# LightController.net
KiCad netlist of a schematic drawn in EAGLE
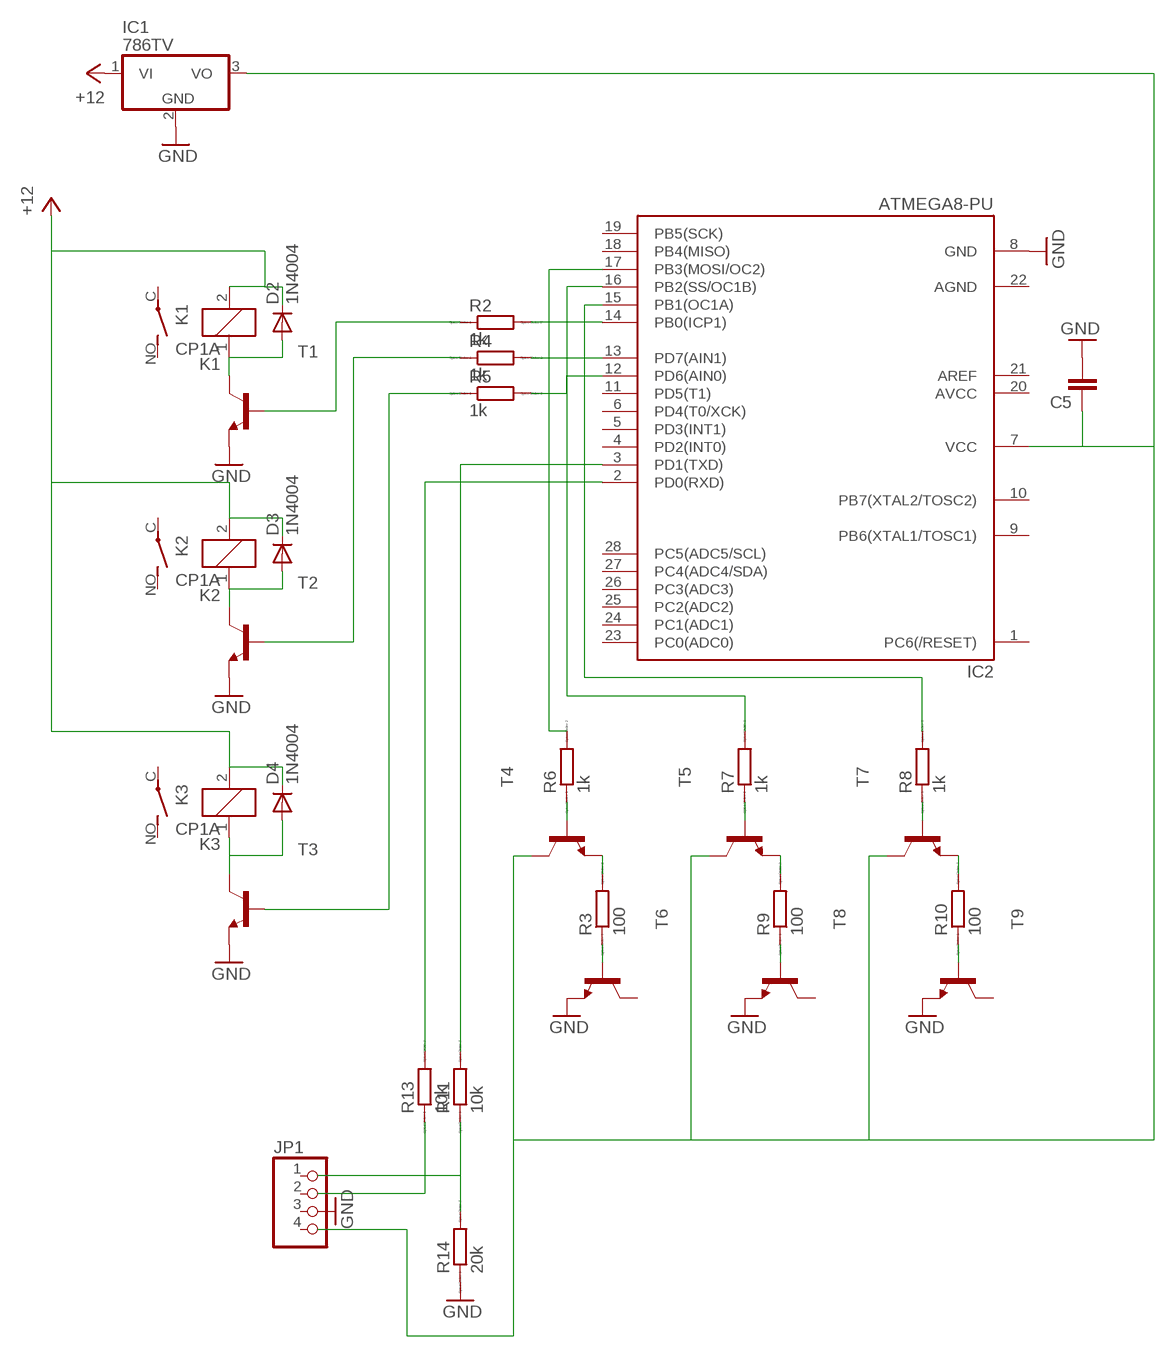
[diagram p0: schematic, sheet 1]

(export (version "E")
  (design (tool "Eeschema 10.0.6"))
  (components
    (comp (ref "C5")
      (value "C2,5-3")
      (footprint "eagle-import:C2.5-3")
      (libsource (lib "eagle-import") (part "C2,5-3"))
    )
    (comp (ref "D2")
      (value "1N4004")
      (footprint "eagle-import:DO41-10")
      (libsource (lib "eagle-import") (part "1N4004"))
    )
    (comp (ref "D3")
      (value "1N4004")
      (footprint "eagle-import:DO41-10")
      (libsource (lib "eagle-import") (part "1N4004"))
    )
    (comp (ref "D4")
      (value "1N4004")
      (footprint "eagle-import:DO41-10")
      (libsource (lib "eagle-import") (part "1N4004"))
    )
    (comp (ref "IC1")
      (value "786TV")
      (footprint "eagle-import:TO220V")
      (libsource (lib "eagle-import") (part "78TV6"))
    )
    (comp (ref "IC2")
      (value "ATMEGA8-PU")
      (footprint "eagle-import:DIL28-3")
      (libsource (lib "eagle-import") (part "ATMEGA8-PU"))
    )
    (comp (ref "JP1")
      (value "PINHD-1X4")
      (footprint "eagle-import:1X04")
      (libsource (lib "eagle-import") (part "PINHD-1X4"))
    )
    (comp (ref "K1")
      (value "CP1A")
      (footprint "eagle-import:CP1A")
      (fields (field (name "MF") "AROMAT/ MATSUSHITA") (field (name "MPN") "CP1A-12V"))
      (libsource (lib "eagle-import") (part "CP1A"))
    )
    (comp (ref "K2")
      (value "CP1A")
      (footprint "eagle-import:CP1A")
      (fields (field (name "MF") "AROMAT/ MATSUSHITA") (field (name "MPN") "CP1A-12V"))
      (libsource (lib "eagle-import") (part "CP1A"))
    )
    (comp (ref "K3")
      (value "CP1A")
      (footprint "eagle-import:CP1A")
      (fields (field (name "MF") "AROMAT/ MATSUSHITA") (field (name "MPN") "CP1A-12V"))
      (libsource (lib "eagle-import") (part "CP1A"))
    )
    (comp (ref "R2")
      (value "1k")
      (footprint "eagle-import:0204_7")
      (libsource (lib "eagle-import") (part "R0204/7"))
    )
    (comp (ref "R3")
      (value "100")
      (footprint "eagle-import:0204_7")
      (libsource (lib "eagle-import") (part "R0204/7"))
    )
    (comp (ref "R4")
      (value "1k")
      (footprint "eagle-import:0204_7")
      (libsource (lib "eagle-import") (part "R0204/7"))
    )
    (comp (ref "R5")
      (value "1k")
      (footprint "eagle-import:0204_7")
      (libsource (lib "eagle-import") (part "R0204/7"))
    )
    (comp (ref "R6")
      (value "1k")
      (footprint "eagle-import:0204_7")
      (libsource (lib "eagle-import") (part "R0204/7"))
    )
    (comp (ref "R7")
      (value "1k")
      (footprint "eagle-import:0204_7")
      (libsource (lib "eagle-import") (part "R0204/7"))
    )
    (comp (ref "R8")
      (value "1k")
      (footprint "eagle-import:0204_7")
      (libsource (lib "eagle-import") (part "R0204/7"))
    )
    (comp (ref "R9")
      (value "100")
      (footprint "eagle-import:0204_7")
      (libsource (lib "eagle-import") (part "R0204/7"))
    )
    (comp (ref "R10")
      (value "100")
      (footprint "eagle-import:0204_7")
      (libsource (lib "eagle-import") (part "R0204/7"))
    )
    (comp (ref "R11")
      (value "10k")
      (footprint "eagle-import:0204_7")
      (libsource (lib "eagle-import") (part "R0204/7"))
    )
    (comp (ref "R13")
      (value "10k")
      (footprint "eagle-import:0204_7")
      (libsource (lib "eagle-import") (part "R0204/7"))
    )
    (comp (ref "R14")
      (value "20k")
      (footprint "eagle-import:0204_7")
      (libsource (lib "eagle-import") (part "R0204/7"))
    )
    (comp (ref "T1")
      (value "-NPN-TO92-EBC")
      (footprint "eagle-import:TO92-EBC")
      (libsource (lib "eagle-import") (part "-NPN-TO92-EBC"))
    )
    (comp (ref "T2")
      (value "-NPN-TO92-EBC")
      (footprint "eagle-import:TO92-EBC")
      (libsource (lib "eagle-import") (part "-NPN-TO92-EBC"))
    )
    (comp (ref "T3")
      (value "-NPN-TO92-EBC")
      (footprint "eagle-import:TO92-EBC")
      (libsource (lib "eagle-import") (part "-NPN-TO92-EBC"))
    )
    (comp (ref "T4")
      (value "-NPN-TO92-EBC")
      (footprint "eagle-import:TO92-EBC")
      (libsource (lib "eagle-import") (part "-NPN-TO92-EBC"))
    )
    (comp (ref "T5")
      (value "-NPN-TO92-EBC")
      (footprint "eagle-import:TO92-EBC")
      (libsource (lib "eagle-import") (part "-NPN-TO92-EBC"))
    )
    (comp (ref "T6")
      (value "BF420-NPN-TO92-BCE")
      (footprint "eagle-import:TO92-BCE")
      (libsource (lib "eagle-import") (part "-NPN-TO92-BCEBF420"))
    )
    (comp (ref "T7")
      (value "-NPN-TO92-EBC")
      (footprint "eagle-import:TO92-EBC")
      (libsource (lib "eagle-import") (part "-NPN-TO92-EBC"))
    )
    (comp (ref "T8")
      (value "BF420-NPN-TO92-BCE")
      (footprint "eagle-import:TO92-BCE")
      (libsource (lib "eagle-import") (part "-NPN-TO92-BCEBF420"))
    )
    (comp (ref "T9")
      (value "BF420-NPN-TO92-BCE")
      (footprint "eagle-import:TO92-BCE")
      (libsource (lib "eagle-import") (part "-NPN-TO92-BCEBF420"))
    )
  )
  (nets
    (net (code "1") (name "+12") (class "Default")
      (node (ref "D2") (pin "C") (pinfunction "C_C") (pintype "passive"))
      (node (ref "D3") (pin "C") (pinfunction "C_C") (pintype "passive"))
      (node (ref "D4") (pin "C") (pinfunction "C_C") (pintype "passive"))
      (node (ref "IC1") (pin "1") (pinfunction "VI_1") (pintype "input"))
      (node (ref "K1") (pin "2") (pinfunction "2_2") (pintype "passive"))
      (node (ref "K2") (pin "2") (pinfunction "2_2") (pintype "passive"))
      (node (ref "K3") (pin "2") (pinfunction "2_2") (pintype "passive"))
    )
    (net (code "2") (name "/AGND") (class "Default")
      (node (ref "IC2") (pin "22") (pinfunction "AGND_22") (pintype "power_in"))
    )
    (net (code "3") (name "GND") (class "Default")
      (node (ref "C5") (pin "2") (pinfunction "2_2") (pintype "passive"))
      (node (ref "IC1") (pin "2") (pinfunction "GND_2") (pintype "passive"))
      (node (ref "IC2") (pin "8") (pinfunction "GND_8") (pintype "power_in"))
      (node (ref "R14") (pin "1") (pinfunction "1_1") (pintype "passive"))
      (node (ref "T1") (pin "E") (pinfunction "E_E") (pintype "passive"))
      (node (ref "T2") (pin "E") (pinfunction "E_E") (pintype "passive"))
      (node (ref "T3") (pin "E") (pinfunction "E_E") (pintype "passive"))
      (node (ref "T6") (pin "E") (pinfunction "E_E") (pintype "passive"))
      (node (ref "T8") (pin "E") (pinfunction "E_E") (pintype "passive"))
      (node (ref "T9") (pin "E") (pinfunction "E_E") (pintype "passive"))
    )
    (net (code "4") (name "Net-(D2-PadA)") (class "Default")
      (node (ref "D2") (pin "A") (pinfunction "A_A") (pintype "passive"))
      (node (ref "K1") (pin "1") (pinfunction "1_1") (pintype "passive"))
      (node (ref "T1") (pin "C") (pinfunction "C_C") (pintype "passive"))
    )
    (net (code "5") (name "Net-(D3-PadA)") (class "Default")
      (node (ref "D3") (pin "A") (pinfunction "A_A") (pintype "passive"))
      (node (ref "K2") (pin "1") (pinfunction "1_1") (pintype "passive"))
      (node (ref "T2") (pin "C") (pinfunction "C_C") (pintype "passive"))
    )
    (net (code "6") (name "Net-(D4-PadA)") (class "Default")
      (node (ref "D4") (pin "A") (pinfunction "A_A") (pintype "passive"))
      (node (ref "K3") (pin "1") (pinfunction "1_1") (pintype "passive"))
      (node (ref "T3") (pin "C") (pinfunction "C_C") (pintype "passive"))
    )
    (net (code "7") (name "Net-(IC1-VO)") (class "Default")
      (node (ref "C5") (pin "1") (pinfunction "1_1") (pintype "passive"))
      (node (ref "IC1") (pin "3") (pinfunction "VO_3") (pintype "passive"))
      (node (ref "IC2") (pin "7") (pinfunction "VCC_7") (pintype "power_in"))
      (node (ref "T4") (pin "C") (pinfunction "C_C") (pintype "passive"))
      (node (ref "T5") (pin "C") (pinfunction "C_C") (pintype "passive"))
      (node (ref "T7") (pin "C") (pinfunction "C_C") (pintype "passive"))
    )
    (net (code "8") (name "Net-(IC2-PB0(ICP1))") (class "Default")
      (node (ref "IC2") (pin "14") (pinfunction "PB0(ICP1)_14") (pintype "bidirectional"))
      (node (ref "R2") (pin "2") (pinfunction "2_2") (pintype "passive"))
    )
    (net (code "9") (name "Net-(IC2-PB1(OC1A))") (class "Default")
      (node (ref "IC2") (pin "15") (pinfunction "PB1(OC1A)_15") (pintype "bidirectional"))
      (node (ref "R8") (pin "2") (pinfunction "2_2") (pintype "passive"))
    )
    (net (code "10") (name "Net-(IC2-PB2(SS{slash}OC1B))") (class "Default")
      (node (ref "IC2") (pin "16") (pinfunction "PB2(SS/OC1B)_16") (pintype "bidirectional"))
      (node (ref "R7") (pin "2") (pinfunction "2_2") (pintype "passive"))
    )
    (net (code "11") (name "Net-(IC2-PB3(MOSI{slash}OC2))") (class "Default")
      (node (ref "IC2") (pin "17") (pinfunction "PB3(MOSI/OC2)_17") (pintype "bidirectional"))
      (node (ref "R6") (pin "2") (pinfunction "2_2") (pintype "passive"))
    )
    (net (code "12") (name "Net-(IC2-PD0(RXD))") (class "Default")
      (node (ref "IC2") (pin "2") (pinfunction "PD0(RXD)_2") (pintype "bidirectional"))
      (node (ref "R13") (pin "2") (pinfunction "2_2") (pintype "passive"))
    )
    (net (code "13") (name "Net-(IC2-PD1(TXD))") (class "Default")
      (node (ref "IC2") (pin "3") (pinfunction "PD1(TXD)_3") (pintype "bidirectional"))
      (node (ref "R11") (pin "2") (pinfunction "2_2") (pintype "passive"))
    )
    (net (code "14") (name "Net-(IC2-PD6(AIN0))") (class "Default")
      (node (ref "IC2") (pin "12") (pinfunction "PD6(AIN0)_12") (pintype "bidirectional"))
      (node (ref "R5") (pin "2") (pinfunction "2_2") (pintype "passive"))
    )
    (net (code "15") (name "Net-(IC2-PD7(AIN1))") (class "Default")
      (node (ref "IC2") (pin "13") (pinfunction "PD7(AIN1)_13") (pintype "bidirectional"))
      (node (ref "R4") (pin "2") (pinfunction "2_2") (pintype "passive"))
    )
    (net (code "16") (name "Net-(R2-Pad1)") (class "Default")
      (node (ref "R2") (pin "1") (pinfunction "1_1") (pintype "passive"))
      (node (ref "T1") (pin "B") (pinfunction "B_B") (pintype "passive"))
    )
    (net (code "17") (name "Net-(R3-Pad1)") (class "Default")
      (node (ref "R3") (pin "1") (pinfunction "1_1") (pintype "passive"))
      (node (ref "T6") (pin "B") (pinfunction "B_B") (pintype "passive"))
    )
    (net (code "18") (name "Net-(R3-Pad2)") (class "Default")
      (node (ref "R3") (pin "2") (pinfunction "2_2") (pintype "passive"))
      (node (ref "T4") (pin "E") (pinfunction "E_E") (pintype "passive"))
    )
    (net (code "19") (name "Net-(R4-Pad1)") (class "Default")
      (node (ref "R4") (pin "1") (pinfunction "1_1") (pintype "passive"))
      (node (ref "T2") (pin "B") (pinfunction "B_B") (pintype "passive"))
    )
    (net (code "20") (name "Net-(R5-Pad1)") (class "Default")
      (node (ref "R5") (pin "1") (pinfunction "1_1") (pintype "passive"))
      (node (ref "T3") (pin "B") (pinfunction "B_B") (pintype "passive"))
    )
    (net (code "21") (name "Net-(R6-Pad1)") (class "Default")
      (node (ref "R6") (pin "1") (pinfunction "1_1") (pintype "passive"))
      (node (ref "T4") (pin "B") (pinfunction "B_B") (pintype "passive"))
    )
    (net (code "22") (name "Net-(R7-Pad1)") (class "Default")
      (node (ref "R7") (pin "1") (pinfunction "1_1") (pintype "passive"))
      (node (ref "T5") (pin "B") (pinfunction "B_B") (pintype "passive"))
    )
    (net (code "23") (name "Net-(R8-Pad1)") (class "Default")
      (node (ref "R8") (pin "1") (pinfunction "1_1") (pintype "passive"))
      (node (ref "T7") (pin "B") (pinfunction "B_B") (pintype "passive"))
    )
    (net (code "24") (name "Net-(R9-Pad1)") (class "Default")
      (node (ref "R9") (pin "1") (pinfunction "1_1") (pintype "passive"))
      (node (ref "T8") (pin "B") (pinfunction "B_B") (pintype "passive"))
    )
    (net (code "25") (name "Net-(R9-Pad2)") (class "Default")
      (node (ref "R9") (pin "2") (pinfunction "2_2") (pintype "passive"))
      (node (ref "T5") (pin "E") (pinfunction "E_E") (pintype "passive"))
    )
    (net (code "26") (name "Net-(R10-Pad1)") (class "Default")
      (node (ref "R10") (pin "1") (pinfunction "1_1") (pintype "passive"))
      (node (ref "T9") (pin "B") (pinfunction "B_B") (pintype "passive"))
    )
    (net (code "27") (name "Net-(R10-Pad2)") (class "Default")
      (node (ref "R10") (pin "2") (pinfunction "2_2") (pintype "passive"))
      (node (ref "T7") (pin "E") (pinfunction "E_E") (pintype "passive"))
    )
    (net (code "28") (name "Net-(R11-Pad1)") (class "Default")
      (node (ref "R11") (pin "1") (pinfunction "1_1") (pintype "passive"))
      (node (ref "R14") (pin "2") (pinfunction "2_2") (pintype "passive"))
    )
    (net (code "29") (name "unconnected-(IC2-AREF-Pad21)") (class "Default")
      (node (ref "IC2") (pin "21") (pinfunction "AREF_21") (pintype "passive"))
    )
    (net (code "30") (name "unconnected-(IC2-AVCC-Pad20)") (class "Default")
      (node (ref "IC2") (pin "20") (pinfunction "AVCC_20") (pintype "passive"))
    )
    (net (code "31") (name "unconnected-(IC2-PB4(MISO)-Pad18)") (class "Default")
      (node (ref "IC2") (pin "18") (pinfunction "PB4(MISO)_18") (pintype "bidirectional"))
    )
    (net (code "32") (name "unconnected-(IC2-PB5(SCK)-Pad19)") (class "Default")
      (node (ref "IC2") (pin "19") (pinfunction "PB5(SCK)_19") (pintype "bidirectional"))
    )
    (net (code "33") (name "unconnected-(IC2-PB6(XTAL1{slash}TOSC1)-Pad9)") (class "Default")
      (node (ref "IC2") (pin "9") (pinfunction "PB6(XTAL1/TOSC1)_9") (pintype "bidirectional"))
    )
    (net (code "34") (name "unconnected-(IC2-PB7(XTAL2{slash}TOSC2)-Pad10)") (class "Default")
      (node (ref "IC2") (pin "10") (pinfunction "PB7(XTAL2/TOSC2)_10") (pintype "bidirectional"))
    )
    (net (code "35") (name "unconnected-(IC2-PC0(ADC0)-Pad23)") (class "Default")
      (node (ref "IC2") (pin "23") (pinfunction "PC0(ADC0)_23") (pintype "bidirectional"))
    )
    (net (code "36") (name "unconnected-(IC2-PC1(ADC1)-Pad24)") (class "Default")
      (node (ref "IC2") (pin "24") (pinfunction "PC1(ADC1)_24") (pintype "bidirectional"))
    )
    (net (code "37") (name "unconnected-(IC2-PC2(ADC2)-Pad25)") (class "Default")
      (node (ref "IC2") (pin "25") (pinfunction "PC2(ADC2)_25") (pintype "bidirectional"))
    )
    (net (code "38") (name "unconnected-(IC2-PC3(ADC3)-Pad26)") (class "Default")
      (node (ref "IC2") (pin "26") (pinfunction "PC3(ADC3)_26") (pintype "bidirectional"))
    )
    (net (code "39") (name "unconnected-(IC2-PC4(ADC4{slash}SDA)-Pad27)") (class "Default")
      (node (ref "IC2") (pin "27") (pinfunction "PC4(ADC4/SDA)_27") (pintype "bidirectional"))
    )
    (net (code "40") (name "unconnected-(IC2-PC5(ADC5{slash}SCL)-Pad28)") (class "Default")
      (node (ref "IC2") (pin "28") (pinfunction "PC5(ADC5/SCL)_28") (pintype "bidirectional"))
    )
    (net (code "41") (name "unconnected-(IC2-PC6({slash}RESET)-Pad1)") (class "Default")
      (node (ref "IC2") (pin "1") (pinfunction "PC6(/RESET)_1") (pintype "bidirectional"))
    )
    (net (code "42") (name "unconnected-(IC2-PD2(INT0)-Pad4)") (class "Default")
      (node (ref "IC2") (pin "4") (pinfunction "PD2(INT0)_4") (pintype "bidirectional"))
    )
    (net (code "43") (name "unconnected-(IC2-PD3(INT1)-Pad5)") (class "Default")
      (node (ref "IC2") (pin "5") (pinfunction "PD3(INT1)_5") (pintype "bidirectional"))
    )
    (net (code "44") (name "unconnected-(IC2-PD4(T0{slash}XCK)-Pad6)") (class "Default")
      (node (ref "IC2") (pin "6") (pinfunction "PD4(T0/XCK)_6") (pintype "bidirectional"))
    )
    (net (code "45") (name "unconnected-(IC2-PD5(T1)-Pad11)") (class "Default")
      (node (ref "IC2") (pin "11") (pinfunction "PD5(T1)_11") (pintype "bidirectional"))
    )
    (net (code "46") (name "unconnected-(JP1-Pad1)") (class "Default")
      (node (ref "JP1") (pin "1") (pinfunction "1_1") (pintype "passive"))
    )
    (net (code "47") (name "unconnected-(JP1-Pad2)") (class "Default")
      (node (ref "JP1") (pin "2") (pinfunction "2_2") (pintype "passive"))
    )
    (net (code "48") (name "unconnected-(JP1-Pad3)") (class "Default")
      (node (ref "JP1") (pin "3") (pinfunction "3_3") (pintype "passive"))
    )
    (net (code "49") (name "unconnected-(JP1-Pad4)") (class "Default")
      (node (ref "JP1") (pin "4") (pinfunction "4_4") (pintype "passive"))
    )
    (net (code "50") (name "unconnected-(K1B-P-PadC)") (class "Default")
      (node (ref "K1") (pin "C") (pinfunction "P_C") (pintype "passive"))
    )
    (net (code "51") (name "unconnected-(K1B-S-PadNO)") (class "Default")
      (node (ref "K1") (pin "NO") (pinfunction "S_NO") (pintype "passive"))
    )
    (net (code "52") (name "unconnected-(K2B-P-PadC)") (class "Default")
      (node (ref "K2") (pin "C") (pinfunction "P_C") (pintype "passive"))
    )
    (net (code "53") (name "unconnected-(K2B-S-PadNO)") (class "Default")
      (node (ref "K2") (pin "NO") (pinfunction "S_NO") (pintype "passive"))
    )
    (net (code "54") (name "unconnected-(K3B-P-PadC)") (class "Default")
      (node (ref "K3") (pin "C") (pinfunction "P_C") (pintype "passive"))
    )
    (net (code "55") (name "unconnected-(K3B-S-PadNO)") (class "Default")
      (node (ref "K3") (pin "NO") (pinfunction "S_NO") (pintype "passive"))
    )
    (net (code "56") (name "unconnected-(R13-Pad1)") (class "Default")
      (node (ref "R13") (pin "1") (pinfunction "1_1") (pintype "passive"))
    )
    (net (code "57") (name "unconnected-(T6-PadC)") (class "Default")
      (node (ref "T6") (pin "C") (pinfunction "C_C") (pintype "passive"))
    )
    (net (code "58") (name "unconnected-(T8-PadC)") (class "Default")
      (node (ref "T8") (pin "C") (pinfunction "C_C") (pintype "passive"))
    )
    (net (code "59") (name "unconnected-(T9-PadC)") (class "Default")
      (node (ref "T9") (pin "C") (pinfunction "C_C") (pintype "passive"))
    )
  )
)
